# proto2board.net
KiCad netlist of a schematic drawn in EAGLE
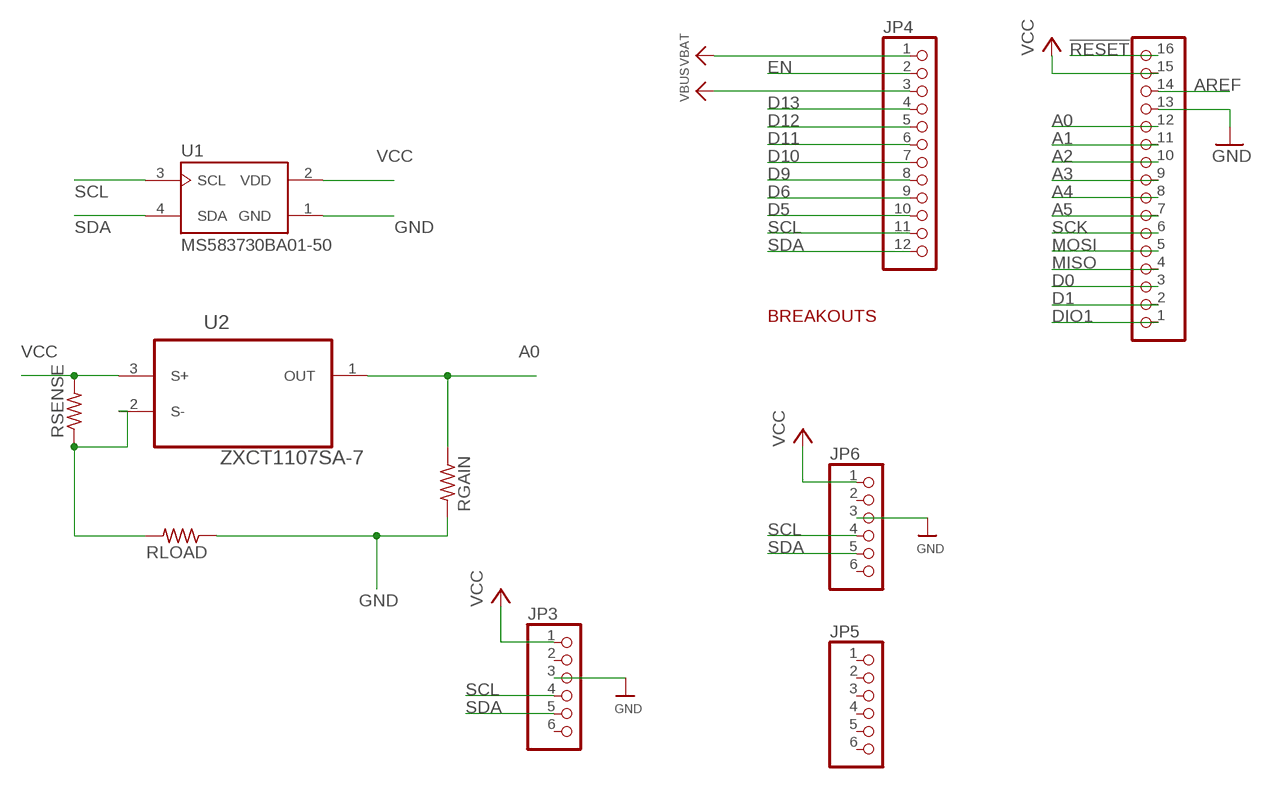
[diagram p0: schematic, sheet 1]

(export (version "E")
  (design (tool "Eeschema 10.0.6"))
  (components
    (comp (ref "JP2")
      (value "HEADER-1X16ROUND")
      (footprint "eagle-import:1X16_ROUND")
      (libsource (lib "eagle-import") (part "HEADER-1X16ROUND"))
    )
    (comp (ref "JP3")
      (value "HEADER-1X670MIL")
      (footprint "eagle-import:1X06_ROUND_70")
      (libsource (lib "eagle-import") (part "HEADER-1X670MIL"))
    )
    (comp (ref "JP4")
      (value "HEADER-1X12")
      (footprint "eagle-import:1X12_ROUND")
      (libsource (lib "eagle-import") (part "HEADER-1X12"))
    )
    (comp (ref "JP5")
      (value "HEADER-1X6ROUND")
      (footprint "eagle-import:1X06_ROUND")
      (libsource (lib "eagle-import") (part "HEADER-1X6ROUND"))
    )
    (comp (ref "JP6")
      (value "HEADER-1X670MIL")
      (footprint "eagle-import:1X06_ROUND_70")
      (libsource (lib "eagle-import") (part "HEADER-1X670MIL"))
    )
    (comp (ref "RGAIN")
      (value "R-US_0204/7")
      (footprint "eagle-import:0204_7")
      (libsource (lib "eagle-import") (part "R-US_0204/7"))
    )
    (comp (ref "RLOAD")
      (value "R-US_0204/7")
      (footprint "eagle-import:0204_7")
      (libsource (lib "eagle-import") (part "R-US_0204/7"))
    )
    (comp (ref "RSENSE")
      (value "R-US_0204/7")
      (footprint "eagle-import:0204_7")
      (libsource (lib "eagle-import") (part "R-US_0204/7"))
    )
    (comp (ref "U1")
      (value "MS583730BA01-50")
      (footprint "eagle-import:TE_MS583730BA01-50")
      (fields (field (name "DIGI-KEY_PART_NUMBER") "223-1704-1-ND") (field (name "MF") "TE Connectivity"))
      (libsource (lib "eagle-import") (part "MS583730BA01-50"))
    )
    (comp (ref "U2")
      (value "ZXCT1107SA-7")
      (footprint "eagle-import:SOT91P240X110-3N")
      (fields (field (name "MF") "Diodes Inc."))
      (libsource (lib "eagle-import") (part "ZXCT1107SA-7"))
    )
  )
  (nets
    (net (code "1") (name "/A0") (class "Default")
      (node (ref "JP2") (pin "12") (pinfunction "12_12") (pintype "passive"))
      (node (ref "RGAIN") (pin "1") (pinfunction "1_1") (pintype "passive"))
      (node (ref "U2") (pin "1") (pinfunction "OUT_1") (pintype "output"))
    )
    (net (code "2") (name "/A1") (class "Default")
      (node (ref "JP2") (pin "11") (pinfunction "11_11") (pintype "passive"))
    )
    (net (code "3") (name "/A2") (class "Default")
      (node (ref "JP2") (pin "10") (pinfunction "10_10") (pintype "passive"))
    )
    (net (code "4") (name "/A3") (class "Default")
      (node (ref "JP2") (pin "9") (pinfunction "9_9") (pintype "passive"))
    )
    (net (code "5") (name "/A4") (class "Default")
      (node (ref "JP2") (pin "8") (pinfunction "8_8") (pintype "passive"))
    )
    (net (code "6") (name "/A5") (class "Default")
      (node (ref "JP2") (pin "7") (pinfunction "7_7") (pintype "passive"))
    )
    (net (code "7") (name "/AREF") (class "Default")
      (node (ref "JP2") (pin "14") (pinfunction "14_14") (pintype "passive"))
    )
    (net (code "8") (name "/D0") (class "Default")
      (node (ref "JP2") (pin "3") (pinfunction "3_3") (pintype "passive"))
    )
    (net (code "9") (name "/D1") (class "Default")
      (node (ref "JP2") (pin "2") (pinfunction "2_2") (pintype "passive"))
    )
    (net (code "10") (name "/D5") (class "Default")
      (node (ref "JP4") (pin "10") (pinfunction "10_10") (pintype "passive"))
    )
    (net (code "11") (name "/D6") (class "Default")
      (node (ref "JP4") (pin "9") (pinfunction "9_9") (pintype "passive"))
    )
    (net (code "12") (name "/D9") (class "Default")
      (node (ref "JP4") (pin "8") (pinfunction "8_8") (pintype "passive"))
    )
    (net (code "13") (name "/D10") (class "Default")
      (node (ref "JP4") (pin "7") (pinfunction "7_7") (pintype "passive"))
    )
    (net (code "14") (name "/D11") (class "Default")
      (node (ref "JP4") (pin "6") (pinfunction "6_6") (pintype "passive"))
    )
    (net (code "15") (name "/D12") (class "Default")
      (node (ref "JP4") (pin "5") (pinfunction "5_5") (pintype "passive"))
    )
    (net (code "16") (name "/D13") (class "Default")
      (node (ref "JP4") (pin "4") (pinfunction "4_4") (pintype "passive"))
    )
    (net (code "17") (name "/DIO1") (class "Default")
      (node (ref "JP2") (pin "1") (pinfunction "1_1") (pintype "passive"))
    )
    (net (code "18") (name "/EN") (class "Default")
      (node (ref "JP4") (pin "2") (pinfunction "2_2") (pintype "passive"))
    )
    (net (code "19") (name "/MISO") (class "Default")
      (node (ref "JP2") (pin "4") (pinfunction "4_4") (pintype "passive"))
    )
    (net (code "20") (name "/MOSI") (class "Default")
      (node (ref "JP2") (pin "5") (pinfunction "5_5") (pintype "passive"))
    )
    (net (code "21") (name "/SCK") (class "Default")
      (node (ref "JP2") (pin "6") (pinfunction "6_6") (pintype "passive"))
    )
    (net (code "22") (name "/SCL") (class "Default")
      (node (ref "JP3") (pin "4") (pinfunction "4_4") (pintype "passive"))
      (node (ref "JP4") (pin "11") (pinfunction "11_11") (pintype "passive"))
      (node (ref "JP6") (pin "4") (pinfunction "4_4") (pintype "passive"))
      (node (ref "U1") (pin "3") (pinfunction "SCL_3") (pintype "input"))
    )
    (net (code "23") (name "/SDA") (class "Default")
      (node (ref "JP3") (pin "5") (pinfunction "5_5") (pintype "passive"))
      (node (ref "JP4") (pin "12") (pinfunction "12_12") (pintype "passive"))
      (node (ref "JP6") (pin "5") (pinfunction "5_5") (pintype "passive"))
      (node (ref "U1") (pin "4") (pinfunction "SDA_4") (pintype "bidirectional"))
    )
    (net (code "24") (name "/~{RESET}") (class "Default")
      (node (ref "JP2") (pin "16") (pinfunction "16_16") (pintype "passive"))
    )
    (net (code "25") (name "GND") (class "Default")
      (node (ref "JP2") (pin "13") (pinfunction "13_13") (pintype "passive"))
      (node (ref "JP3") (pin "3") (pinfunction "3_3") (pintype "passive"))
      (node (ref "JP6") (pin "3") (pinfunction "3_3") (pintype "passive"))
      (node (ref "RGAIN") (pin "2") (pinfunction "2_2") (pintype "passive"))
      (node (ref "RLOAD") (pin "1") (pinfunction "1_1") (pintype "passive"))
      (node (ref "U1") (pin "1") (pinfunction "GND_1") (pintype "power_in"))
    )
    (net (code "26") (name "Net-(U2-S-)") (class "Default")
      (node (ref "RLOAD") (pin "2") (pinfunction "2_2") (pintype "passive"))
      (node (ref "RSENSE") (pin "1") (pinfunction "1_1") (pintype "passive"))
      (node (ref "U2") (pin "2") (pinfunction "S-_2") (pintype "input"))
    )
    (net (code "27") (name "VBAT") (class "Default")
      (node (ref "JP4") (pin "1") (pinfunction "1_1") (pintype "passive"))
    )
    (net (code "28") (name "VBUS") (class "Default")
      (node (ref "JP4") (pin "3") (pinfunction "3_3") (pintype "passive"))
    )
    (net (code "29") (name "VCC") (class "Default")
      (node (ref "JP2") (pin "15") (pinfunction "15_15") (pintype "passive"))
      (node (ref "JP3") (pin "1") (pinfunction "1_1") (pintype "passive"))
      (node (ref "JP6") (pin "1") (pinfunction "1_1") (pintype "passive"))
      (node (ref "RSENSE") (pin "2") (pinfunction "2_2") (pintype "passive"))
      (node (ref "U1") (pin "2") (pinfunction "VDD_2") (pintype "power_in"))
      (node (ref "U2") (pin "3") (pinfunction "S+_3") (pintype "input"))
    )
    (net (code "30") (name "unconnected-(JP3-Pad2)") (class "Default")
      (node (ref "JP3") (pin "2") (pinfunction "2_2") (pintype "passive"))
    )
    (net (code "31") (name "unconnected-(JP3-Pad6)") (class "Default")
      (node (ref "JP3") (pin "6") (pinfunction "6_6") (pintype "passive"))
    )
    (net (code "32") (name "unconnected-(JP5-Pad1)") (class "Default")
      (node (ref "JP5") (pin "1") (pinfunction "1_1") (pintype "passive"))
    )
    (net (code "33") (name "unconnected-(JP5-Pad2)") (class "Default")
      (node (ref "JP5") (pin "2") (pinfunction "2_2") (pintype "passive"))
    )
    (net (code "34") (name "unconnected-(JP5-Pad3)") (class "Default")
      (node (ref "JP5") (pin "3") (pinfunction "3_3") (pintype "passive"))
    )
    (net (code "35") (name "unconnected-(JP5-Pad4)") (class "Default")
      (node (ref "JP5") (pin "4") (pinfunction "4_4") (pintype "passive"))
    )
    (net (code "36") (name "unconnected-(JP5-Pad5)") (class "Default")
      (node (ref "JP5") (pin "5") (pinfunction "5_5") (pintype "passive"))
    )
    (net (code "37") (name "unconnected-(JP5-Pad6)") (class "Default")
      (node (ref "JP5") (pin "6") (pinfunction "6_6") (pintype "passive"))
    )
    (net (code "38") (name "unconnected-(JP6-Pad2)") (class "Default")
      (node (ref "JP6") (pin "2") (pinfunction "2_2") (pintype "passive"))
    )
    (net (code "39") (name "unconnected-(JP6-Pad6)") (class "Default")
      (node (ref "JP6") (pin "6") (pinfunction "6_6") (pintype "passive"))
    )
  )
)
